# ExpansionConnector.net
KiCad netlist of a schematic drawn in Altium Designer
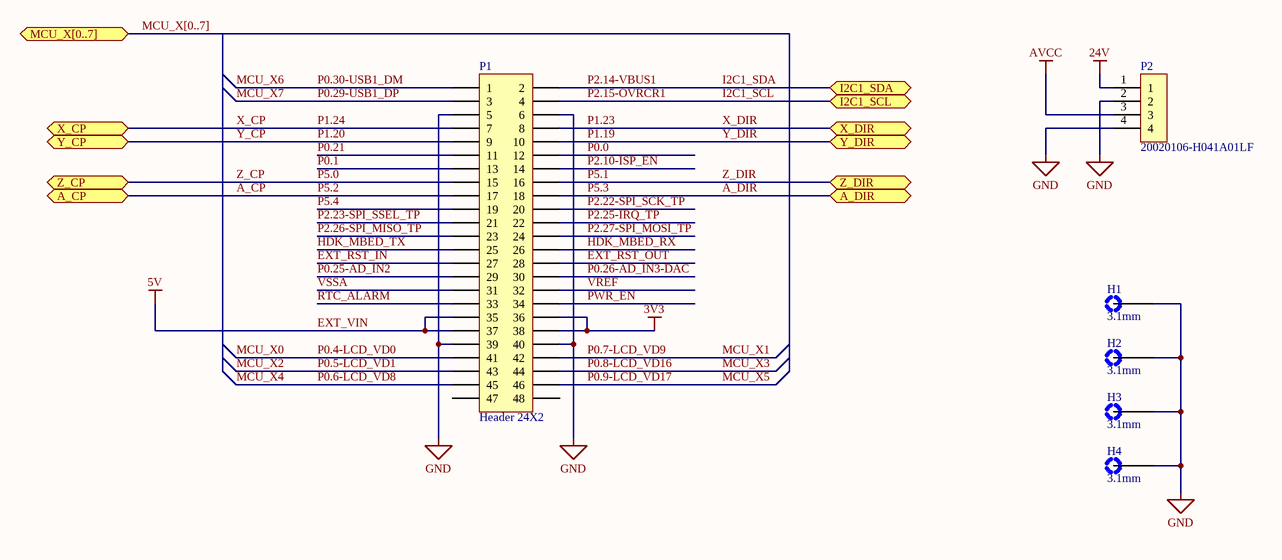
[diagram p0: ExpansionConnector.SchDoc]

(export (version "E")
  (design (tool "Eeschema 10.0.6"))
  (components
    (comp (ref "H1")
      (value "3.1mm")
      (footprint "PcbLib:Holes")
      (description "Mounting Holes")
      (libsource (lib "Schlib") (part "Holes"))
    )
    (comp (ref "H2")
      (value "3.1mm")
      (footprint "PcbLib:Holes")
      (description "Mounting Holes")
      (libsource (lib "Schlib") (part "Holes"))
    )
    (comp (ref "H3")
      (value "3.1mm")
      (footprint "PcbLib:Holes")
      (description "Mounting Holes")
      (libsource (lib "Schlib") (part "Holes"))
    )
    (comp (ref "H4")
      (value "3.1mm")
      (footprint "PcbLib:Holes")
      (description "Mounting Holes")
      (libsource (lib "Schlib") (part "Holes"))
    )
    (comp (ref "P1")
      (value "Header 24X2")
      (footprint "HDR2X24")
      (description "Header, 24-Pin, Dual row")
      (fields (field (name "PUBLISHER") "Altium Limited"))
      (libsource (lib "Miscellaneous Connectors") (part "Header 24X2"))
    )
    (comp (ref "P2")
      (value "20020106-H041A01LF")
      (footprint "Connectors:20020106-H041A01LF")
      (description "TERM BLOCK HDR 4POS VERT 5.08MM")
      (libsource (lib "Connectors") (part "Amphenol FCI"))
    )
  )
  (nets
    (net (code "1") (name "/A_CP") (class "Default")
      (node (ref "P1") (pin "17") (pinfunction "17_17") (pintype "passive"))
    )
    (net (code "2") (name "/A_DIR") (class "Default")
      (node (ref "P1") (pin "18") (pinfunction "18_18") (pintype "passive"))
    )
    (net (code "3") (name "/EXT_RST_IN") (class "Default")
      (node (ref "P1") (pin "27") (pinfunction "27_27") (pintype "passive"))
    )
    (net (code "4") (name "/EXT_RST_OUT") (class "Default")
      (node (ref "P1") (pin "28") (pinfunction "28_28") (pintype "passive"))
    )
    (net (code "5") (name "/HDK_MBED_RX") (class "Default")
      (node (ref "P1") (pin "26") (pinfunction "26_26") (pintype "passive"))
    )
    (net (code "6") (name "/HDK_MBED_TX") (class "Default")
      (node (ref "P1") (pin "25") (pinfunction "25_25") (pintype "passive"))
    )
    (net (code "7") (name "/I2C1_SCL") (class "Default")
      (node (ref "P1") (pin "4") (pinfunction "4_4") (pintype "passive"))
    )
    (net (code "8") (name "/I2C1_SDA") (class "Default")
      (node (ref "P1") (pin "2") (pinfunction "2_2") (pintype "passive"))
    )
    (net (code "9") (name "/MCU_X0") (class "Default")
      (node (ref "P1") (pin "41") (pinfunction "41_41") (pintype "passive"))
    )
    (net (code "10") (name "/MCU_X1") (class "Default")
      (node (ref "P1") (pin "42") (pinfunction "42_42") (pintype "passive"))
    )
    (net (code "11") (name "/MCU_X2") (class "Default")
      (node (ref "P1") (pin "43") (pinfunction "43_43") (pintype "passive"))
    )
    (net (code "12") (name "/MCU_X3") (class "Default")
      (node (ref "P1") (pin "44") (pinfunction "44_44") (pintype "passive"))
    )
    (net (code "13") (name "/MCU_X4") (class "Default")
      (node (ref "P1") (pin "45") (pinfunction "45_45") (pintype "passive"))
    )
    (net (code "14") (name "/MCU_X5") (class "Default")
      (node (ref "P1") (pin "46") (pinfunction "46_46") (pintype "passive"))
    )
    (net (code "15") (name "/MCU_X6") (class "Default")
      (node (ref "P1") (pin "1") (pinfunction "1_1") (pintype "passive"))
    )
    (net (code "16") (name "/MCU_X7") (class "Default")
      (node (ref "P1") (pin "3") (pinfunction "3_3") (pintype "passive"))
    )
    (net (code "18") (name "/P0.0") (class "Default")
      (node (ref "P1") (pin "12") (pinfunction "12_12") (pintype "passive"))
    )
    (net (code "19") (name "/P0.1") (class "Default")
      (node (ref "P1") (pin "13") (pinfunction "13_13") (pintype "passive"))
    )
    (net (code "20") (name "/P0.21") (class "Default")
      (node (ref "P1") (pin "11") (pinfunction "11_11") (pintype "passive"))
    )
    (net (code "21") (name "/P0.25-AD_IN2") (class "Default")
      (node (ref "P1") (pin "29") (pinfunction "29_29") (pintype "passive"))
    )
    (net (code "22") (name "/P0.26-AD_IN3-DAC") (class "Default")
      (node (ref "P1") (pin "30") (pinfunction "30_30") (pintype "passive"))
    )
    (net (code "23") (name "/P1.19") (class "Default")
      (node (ref "P1") (pin "10") (pinfunction "10_10") (pintype "passive"))
    )
    (net (code "24") (name "/P1.20") (class "Default")
      (node (ref "P1") (pin "9") (pinfunction "9_9") (pintype "passive"))
    )
    (net (code "25") (name "/P1.23") (class "Default")
      (node (ref "P1") (pin "8") (pinfunction "8_8") (pintype "passive"))
    )
    (net (code "26") (name "/P1.24") (class "Default")
      (node (ref "P1") (pin "7") (pinfunction "7_7") (pintype "passive"))
    )
    (net (code "27") (name "/P2.10-ISP_EN") (class "Default")
      (node (ref "P1") (pin "14") (pinfunction "14_14") (pintype "passive"))
    )
    (net (code "28") (name "/P2.22-SPI_SCK_TP") (class "Default")
      (node (ref "P1") (pin "20") (pinfunction "20_20") (pintype "passive"))
    )
    (net (code "29") (name "/P2.23-SPI_SSEL_TP") (class "Default")
      (node (ref "P1") (pin "21") (pinfunction "21_21") (pintype "passive"))
    )
    (net (code "30") (name "/P2.25-IRQ_TP") (class "Default")
      (node (ref "P1") (pin "22") (pinfunction "22_22") (pintype "passive"))
    )
    (net (code "31") (name "/P2.26-SPI_MISO_TP") (class "Default")
      (node (ref "P1") (pin "23") (pinfunction "23_23") (pintype "passive"))
    )
    (net (code "32") (name "/P2.27-SPI_MOSI_TP") (class "Default")
      (node (ref "P1") (pin "24") (pinfunction "24_24") (pintype "passive"))
    )
    (net (code "33") (name "/P5.0") (class "Default")
      (node (ref "P1") (pin "15") (pinfunction "15_15") (pintype "passive"))
    )
    (net (code "34") (name "/P5.1") (class "Default")
      (node (ref "P1") (pin "16") (pinfunction "16_16") (pintype "passive"))
    )
    (net (code "35") (name "/P5.4") (class "Default")
      (node (ref "P1") (pin "19") (pinfunction "19_19") (pintype "passive"))
    )
    (net (code "36") (name "/PWR_EN") (class "Default")
      (node (ref "P1") (pin "34") (pinfunction "34_34") (pintype "passive"))
    )
    (net (code "37") (name "/RTC_ALARM") (class "Default")
      (node (ref "P1") (pin "33") (pinfunction "33_33") (pintype "passive"))
    )
    (net (code "38") (name "/VREF") (class "Default")
      (node (ref "P1") (pin "32") (pinfunction "32_32") (pintype "passive"))
    )
    (net (code "39") (name "/VSSA") (class "Default")
      (node (ref "P1") (pin "31") (pinfunction "31_31") (pintype "passive"))
    )
    (net (code "40") (name "3V3") (class "Default")
      (node (ref "P1") (pin "36") (pinfunction "36_36") (pintype "passive"))
      (node (ref "P1") (pin "38") (pinfunction "38_38") (pintype "passive"))
    )
    (net (code "41") (name "5V") (class "Default")
      (node (ref "P1") (pin "35") (pinfunction "35_35") (pintype "passive"))
      (node (ref "P1") (pin "37") (pinfunction "37_37") (pintype "passive"))
    )
    (net (code "42") (name "24V") (class "Default")
      (node (ref "P2") (pin "1") (pinfunction "1_1") (pintype "passive"))
    )
    (net (code "43") (name "AVCC") (class "Default")
      (node (ref "P2") (pin "3") (pinfunction "3_3") (pintype "passive"))
    )
    (net (code "44") (name "GND") (class "Default")
      (node (ref "H1") (pin "0") (pinfunction "0_0") (pintype "passive"))
      (node (ref "H2") (pin "0") (pinfunction "0_0") (pintype "passive"))
      (node (ref "H3") (pin "0") (pinfunction "0_0") (pintype "passive"))
      (node (ref "H4") (pin "0") (pinfunction "0_0") (pintype "passive"))
      (node (ref "P1") (pin "39") (pinfunction "39_39") (pintype "passive"))
      (node (ref "P1") (pin "40") (pinfunction "40_40") (pintype "passive"))
      (node (ref "P1") (pin "5") (pinfunction "5_5") (pintype "passive"))
      (node (ref "P1") (pin "6") (pinfunction "6_6") (pintype "passive"))
      (node (ref "P2") (pin "2") (pinfunction "2_2") (pintype "passive"))
      (node (ref "P2") (pin "4") (pinfunction "4_4") (pintype "passive"))
    )
    (net (code "45") (name "unconnected-(P1-Pad47)") (class "Default")
      (node (ref "P1") (pin "47") (pinfunction "47_47") (pintype "passive"))
    )
    (net (code "46") (name "unconnected-(P1-Pad48)") (class "Default")
      (node (ref "P1") (pin "48") (pinfunction "48_48") (pintype "passive"))
    )
  )
)
